# cry.net
KiCad netlist of a schematic drawn in EAGLE
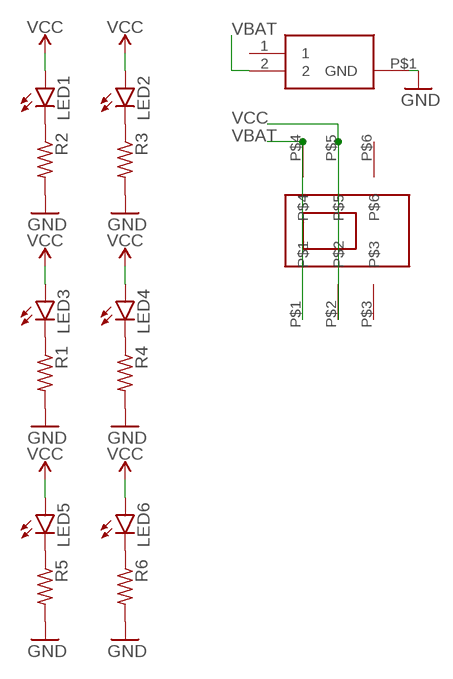
[diagram p0: schematic, sheet 1]

(export (version "E")
  (design (tool "Eeschema 10.0.6"))
  (components
    (comp (ref "LED1")
      (value "LEDCHIP-LED0805")
      (footprint "eagle-import:CHIP-LED0805")
      (libsource (lib "eagle-import") (part "LEDCHIP-LED0805"))
    )
    (comp (ref "LED2")
      (value "LEDCHIP-LED0805")
      (footprint "eagle-import:CHIP-LED0805")
      (libsource (lib "eagle-import") (part "LEDCHIP-LED0805"))
    )
    (comp (ref "LED3")
      (value "LEDCHIP-LED0805")
      (footprint "eagle-import:CHIP-LED0805")
      (libsource (lib "eagle-import") (part "LEDCHIP-LED0805"))
    )
    (comp (ref "LED4")
      (value "LEDCHIP-LED0805")
      (footprint "eagle-import:CHIP-LED0805")
      (libsource (lib "eagle-import") (part "LEDCHIP-LED0805"))
    )
    (comp (ref "LED5")
      (value "LEDCHIP-LED0805")
      (footprint "eagle-import:CHIP-LED0805")
      (libsource (lib "eagle-import") (part "LEDCHIP-LED0805"))
    )
    (comp (ref "LED6")
      (value "LEDCHIP-LED0805")
      (footprint "eagle-import:CHIP-LED0805")
      (libsource (lib "eagle-import") (part "LEDCHIP-LED0805"))
    )
    (comp (ref "R1")
      (value "R-US_R0603")
      (footprint "eagle-import:R0603")
      (libsource (lib "eagle-import") (part "R-US_R0603"))
    )
    (comp (ref "R2")
      (value "R-US_R0603")
      (footprint "eagle-import:R0603")
      (libsource (lib "eagle-import") (part "R-US_R0603"))
    )
    (comp (ref "R3")
      (value "R-US_R0603")
      (footprint "eagle-import:R0603")
      (libsource (lib "eagle-import") (part "R-US_R0603"))
    )
    (comp (ref "R4")
      (value "R-US_R0603")
      (footprint "eagle-import:R0603")
      (libsource (lib "eagle-import") (part "R-US_R0603"))
    )
    (comp (ref "R5")
      (value "R-US_R0603")
      (footprint "eagle-import:R0603")
      (libsource (lib "eagle-import") (part "R-US_R0603"))
    )
    (comp (ref "R6")
      (value "R-US_R0603")
      (footprint "eagle-import:R0603")
      (libsource (lib "eagle-import") (part "R-US_R0603"))
    )
    (comp (ref "U$1")
      (value "CL-SB-22A-02T-SLIDE-SWITCH-TUCKED-PADS")
      (footprint "eagle-import:CL-SB-22A-02T-DPDT-COMPACT-SWITCH")
      (libsource (lib "eagle-import") (part "CL-SB-22A-02T-SLIDE-SWITCH-TUCKED-PADS"))
    )
    (comp (ref "VBAT")
      (value "BAT-HLD-012-SMT")
      (footprint "eagle-import:BATHLD012SMT")
      (fields (field (name "MOUSER_PART_NUMBER") "712-BAT-HLD-012-SMT"))
      (libsource (lib "eagle-import") (part "BAT-HLD-012-SMT"))
    )
  )
  (nets
    (net (code "1") (name "/VBAT") (class "Default")
      (node (ref "U$1") (pin "P$1") (pinfunction "P$1_P$1") (pintype "bidirectional"))
      (node (ref "U$1") (pin "P$4") (pinfunction "P$4_P$4") (pintype "bidirectional"))
      (node (ref "VBAT") (pin "2") (pinfunction "2_2") (pintype "bidirectional"))
    )
    (net (code "2") (name "GND") (class "Default")
      (node (ref "R1") (pin "2") (pinfunction "2_2") (pintype "passive"))
      (node (ref "R2") (pin "2") (pinfunction "2_2") (pintype "passive"))
      (node (ref "R3") (pin "2") (pinfunction "2_2") (pintype "passive"))
      (node (ref "R4") (pin "2") (pinfunction "2_2") (pintype "passive"))
      (node (ref "R5") (pin "2") (pinfunction "2_2") (pintype "passive"))
      (node (ref "R6") (pin "2") (pinfunction "2_2") (pintype "passive"))
      (node (ref "VBAT") (pin "P$1") (pinfunction "GND_P$1") (pintype "bidirectional"))
    )
    (net (code "3") (name "Net-(LED1-PadC)") (class "Default")
      (node (ref "LED1") (pin "C") (pinfunction "C_C") (pintype "passive"))
      (node (ref "R2") (pin "1") (pinfunction "1_1") (pintype "passive"))
    )
    (net (code "4") (name "Net-(LED2-PadC)") (class "Default")
      (node (ref "LED2") (pin "C") (pinfunction "C_C") (pintype "passive"))
      (node (ref "R3") (pin "1") (pinfunction "1_1") (pintype "passive"))
    )
    (net (code "5") (name "Net-(LED3-PadC)") (class "Default")
      (node (ref "LED3") (pin "C") (pinfunction "C_C") (pintype "passive"))
      (node (ref "R1") (pin "1") (pinfunction "1_1") (pintype "passive"))
    )
    (net (code "6") (name "Net-(LED4-PadC)") (class "Default")
      (node (ref "LED4") (pin "C") (pinfunction "C_C") (pintype "passive"))
      (node (ref "R4") (pin "1") (pinfunction "1_1") (pintype "passive"))
    )
    (net (code "7") (name "Net-(LED5-PadC)") (class "Default")
      (node (ref "LED5") (pin "C") (pinfunction "C_C") (pintype "passive"))
      (node (ref "R5") (pin "1") (pinfunction "1_1") (pintype "passive"))
    )
    (net (code "8") (name "Net-(LED6-PadC)") (class "Default")
      (node (ref "LED6") (pin "C") (pinfunction "C_C") (pintype "passive"))
      (node (ref "R6") (pin "1") (pinfunction "1_1") (pintype "passive"))
    )
    (net (code "9") (name "VCC") (class "Default")
      (node (ref "LED1") (pin "A") (pinfunction "A_A") (pintype "passive"))
      (node (ref "LED2") (pin "A") (pinfunction "A_A") (pintype "passive"))
      (node (ref "LED3") (pin "A") (pinfunction "A_A") (pintype "passive"))
      (node (ref "LED4") (pin "A") (pinfunction "A_A") (pintype "passive"))
      (node (ref "LED5") (pin "A") (pinfunction "A_A") (pintype "passive"))
      (node (ref "LED6") (pin "A") (pinfunction "A_A") (pintype "passive"))
      (node (ref "U$1") (pin "P$2") (pinfunction "P$2_P$2") (pintype "bidirectional"))
      (node (ref "U$1") (pin "P$5") (pinfunction "P$5_P$5") (pintype "bidirectional"))
    )
    (net (code "10") (name "unconnected-(U$1-PadP$3)") (class "Default")
      (node (ref "U$1") (pin "P$3") (pinfunction "P$3_P$3") (pintype "bidirectional"))
    )
    (net (code "11") (name "unconnected-(U$1-PadP$6)") (class "Default")
      (node (ref "U$1") (pin "P$6") (pinfunction "P$6_P$6") (pintype "bidirectional"))
    )
    (net (code "12") (name "unconnected-(VBAT-Pad1)") (class "Default")
      (node (ref "VBAT") (pin "1") (pinfunction "1_1") (pintype "bidirectional"))
    )
  )
)
